# WiFiNode_Per_R00.net
KiCad netlist of a schematic drawn in Altium Designer
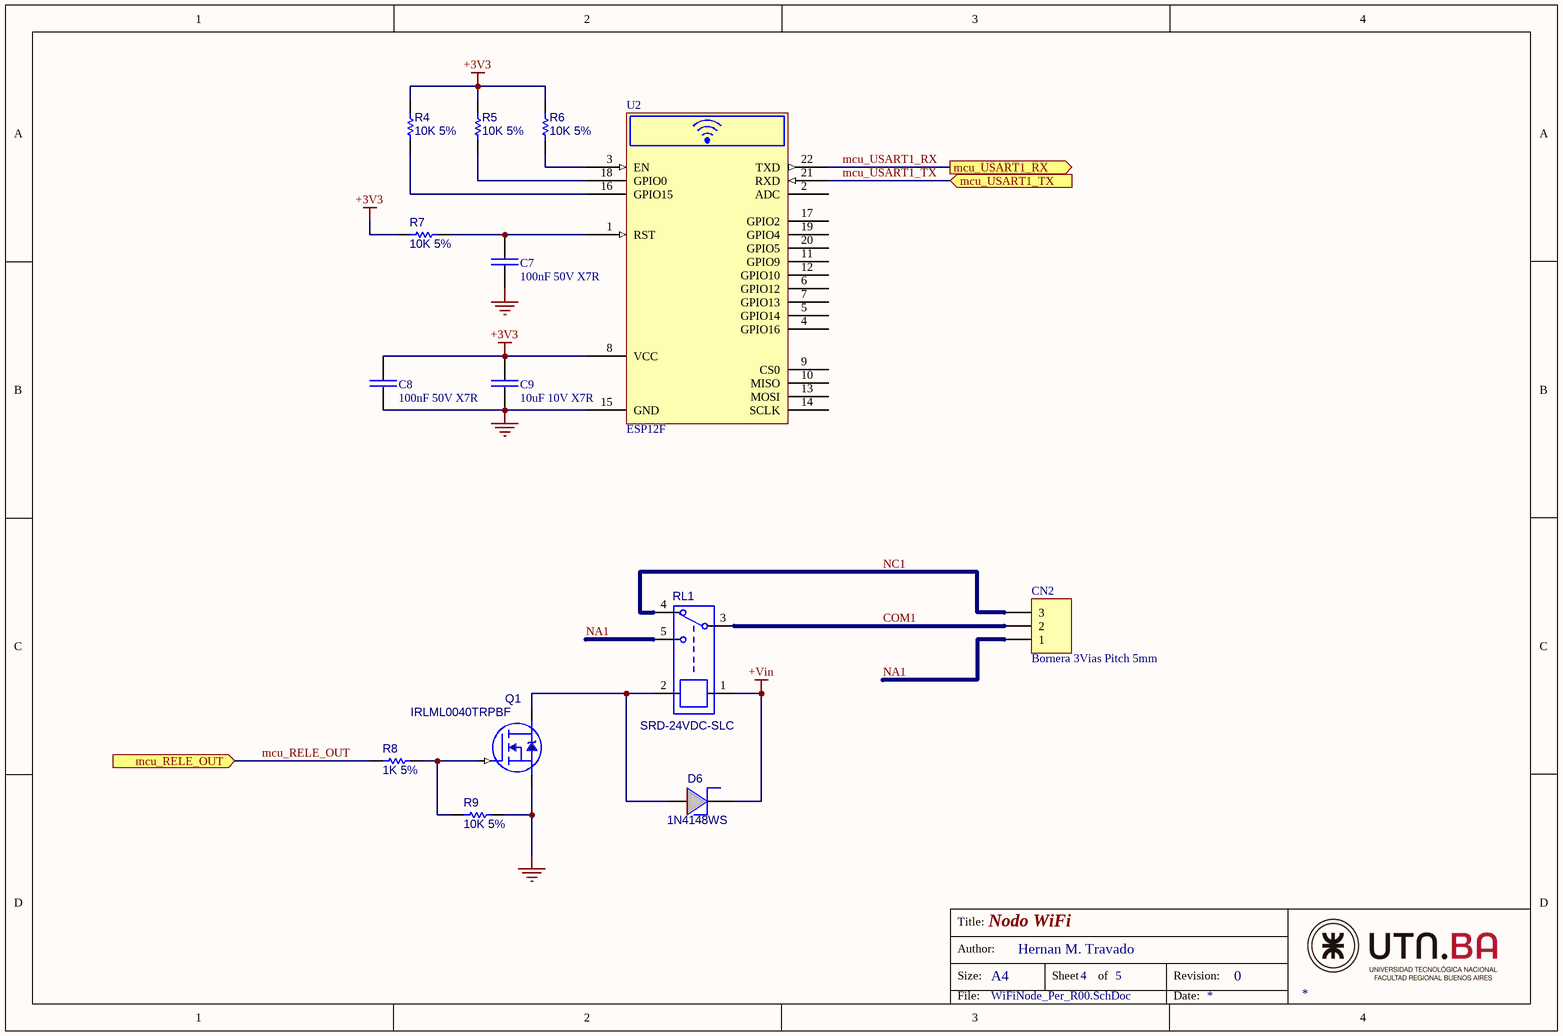
[diagram p0: WiFiNode_Per_R00.SchDoc]

(export (version "E")
  (design (tool "Eeschema 10.0.6"))
  (components
    (comp (ref "C7")
      (value "100nF 50V X7R")
      (footprint "C_0805")
      (description "Ceramic Capacitor")
      (libsource (lib "WiFiNode_R00") (part "Ceramic capacitor"))
    )
    (comp (ref "C8")
      (value "100nF 50V X7R")
      (footprint "C_0805")
      (description "Ceramic Capacitor")
      (libsource (lib "WiFiNode_R00") (part "Ceramic capacitor"))
    )
    (comp (ref "C9")
      (value "10uF 10V X7R")
      (footprint "C_0805")
      (description "Ceramic Capacitor")
      (libsource (lib "WiFiNode_R00") (part "Ceramic capacitor"))
    )
    (comp (ref "CN2")
      (value "Bornera 3Vias Pitch 5mm")
      (footprint "TerminalBlock_1x3_P5mm")
      (description "Connector Generic 3 Vias")
      (libsource (lib "WiFiNode_R00") (part "CONN_03P"))
    )
    (comp (ref "D6")
      (value "1N4148WS")
      (footprint "SOD_323")
      (description "Diode Shottky")
      (libsource (lib "WiFiNode_R00") (part "DIODO_SH"))
    )
    (comp (ref "Q1")
      (value "IRLML0040TRPBF")
      (footprint "SOT_23")
      (description "Mosfet N-Ch")
      (libsource (lib "WiFiNode_R00") (part "N_MOSFET_SOT23"))
    )
    (comp (ref "R4")
      (value "10K 5%")
      (footprint "R_0805")
      (description "Resistor")
      (libsource (lib "WiFiNode_R00") (part "Res1"))
    )
    (comp (ref "R5")
      (value "10K 5%")
      (footprint "R_0805")
      (description "Resistor")
      (libsource (lib "WiFiNode_R00") (part "Res1"))
    )
    (comp (ref "R6")
      (value "10K 5%")
      (footprint "R_0805")
      (description "Resistor")
      (libsource (lib "WiFiNode_R00") (part "Res1"))
    )
    (comp (ref "R7")
      (value "10K 5%")
      (footprint "R_0805")
      (description "Resistor")
      (libsource (lib "WiFiNode_R00") (part "Res1"))
    )
    (comp (ref "R8")
      (value "1K 5%")
      (footprint "R_0805")
      (description "Resistor")
      (libsource (lib "WiFiNode_R00") (part "Res1"))
    )
    (comp (ref "R9")
      (value "10K 5%")
      (footprint "R_0805")
      (description "Resistor")
      (libsource (lib "WiFiNode_R00") (part "Res1"))
    )
    (comp (ref "RL1")
      (value "SRD-24VDC-SLC")
      (footprint "943-1C")
      (description "Relay SPDT")
      (libsource (lib "WiFiNode_R00") (part "RELAY SPDT"))
    )
    (comp (ref "U2")
      (value "ESP12F")
      (footprint "ESP12F")
      (description "Wifi Module")
      (libsource (lib "WiFiNode_R00") (part "ESP12F Wifi Module"))
    )
  )
  (nets
    (net (code "1") (name "+3V3") (class "Default")
      (node (ref "C8") (pin "1") (pinfunction "1_1") (pintype "passive"))
      (node (ref "C9") (pin "1") (pinfunction "1_1") (pintype "passive"))
      (node (ref "R4") (pin "2") (pinfunction "2_2") (pintype "passive"))
      (node (ref "R5") (pin "2") (pinfunction "2_2") (pintype "passive"))
      (node (ref "R6") (pin "2") (pinfunction "2_2") (pintype "passive"))
      (node (ref "R7") (pin "2") (pinfunction "2_2") (pintype "passive"))
      (node (ref "U2") (pin "8") (pinfunction "VCC_8") (pintype "power_in"))
    )
    (net (code "2") (name "+Vin") (class "Default")
      (node (ref "D6") (pin "2") (pinfunction "K_2") (pintype "passive"))
      (node (ref "RL1") (pin "1") (pinfunction "1_1") (pintype "passive"))
    )
    (net (code "3") (name "/COM1") (class "Default")
      (node (ref "CN2") (pin "2") (pinfunction "2_2") (pintype "passive"))
      (node (ref "RL1") (pin "3") (pinfunction "3_3") (pintype "passive"))
    )
    (net (code "4") (name "/NA1") (class "Default")
      (node (ref "CN2") (pin "1") (pinfunction "1_1") (pintype "passive"))
      (node (ref "RL1") (pin "5") (pinfunction "5_5") (pintype "passive"))
    )
    (net (code "5") (name "/NC1") (class "Default")
      (node (ref "CN2") (pin "3") (pinfunction "3_3") (pintype "passive"))
      (node (ref "RL1") (pin "4") (pinfunction "4_4") (pintype "passive"))
    )
    (net (code "6") (name "/mcu_RELE_OUT") (class "Default")
      (node (ref "R8") (pin "2") (pinfunction "2_2") (pintype "passive"))
    )
    (net (code "7") (name "/mcu_USART1_RX") (class "Default")
      (node (ref "U2") (pin "22") (pinfunction "TXD_22") (pintype "output"))
    )
    (net (code "8") (name "/mcu_USART1_TX") (class "Default")
      (node (ref "U2") (pin "21") (pinfunction "RXD_21") (pintype "input"))
    )
    (net (code "9") (name "GND") (class "Default")
      (node (ref "C7") (pin "2") (pinfunction "2_2") (pintype "passive"))
      (node (ref "C8") (pin "2") (pinfunction "2_2") (pintype "passive"))
      (node (ref "C9") (pin "2") (pinfunction "2_2") (pintype "passive"))
      (node (ref "Q1") (pin "2") (pinfunction "SOURCE_2") (pintype "passive"))
      (node (ref "R9") (pin "1") (pinfunction "1_1") (pintype "passive"))
      (node (ref "U2") (pin "15") (pinfunction "GND_15") (pintype "power_in"))
    )
    (net (code "10") (name "Net-(D6-A)") (class "Default")
      (node (ref "D6") (pin "1") (pinfunction "A_1") (pintype "passive"))
      (node (ref "Q1") (pin "3") (pinfunction "DRAIN_3") (pintype "passive"))
      (node (ref "RL1") (pin "2") (pinfunction "2_2") (pintype "passive"))
    )
    (net (code "11") (name "Net-(Q1-GATE)") (class "Default")
      (node (ref "Q1") (pin "1") (pinfunction "GATE_1") (pintype "input"))
      (node (ref "R8") (pin "1") (pinfunction "1_1") (pintype "passive"))
      (node (ref "R9") (pin "2") (pinfunction "2_2") (pintype "passive"))
    )
    (net (code "12") (name "Net-(U2-EN)") (class "Default")
      (node (ref "R6") (pin "1") (pinfunction "1_1") (pintype "passive"))
      (node (ref "U2") (pin "3") (pinfunction "EN_3") (pintype "input"))
    )
    (net (code "13") (name "Net-(U2-GPIO0)") (class "Default")
      (node (ref "R5") (pin "1") (pinfunction "1_1") (pintype "passive"))
      (node (ref "U2") (pin "18") (pinfunction "GPIO0_18") (pintype "passive"))
    )
    (net (code "14") (name "Net-(U2-GPIO15)") (class "Default")
      (node (ref "R4") (pin "1") (pinfunction "1_1") (pintype "passive"))
      (node (ref "U2") (pin "16") (pinfunction "GPIO15_16") (pintype "passive"))
    )
    (net (code "15") (name "Net-(U2-RST)") (class "Default")
      (node (ref "C7") (pin "1") (pinfunction "1_1") (pintype "passive"))
      (node (ref "R7") (pin "1") (pinfunction "1_1") (pintype "passive"))
      (node (ref "U2") (pin "1") (pinfunction "RST_1") (pintype "input"))
    )
    (net (code "16") (name "unconnected-(U2-ADC-Pad2)") (class "Default")
      (node (ref "U2") (pin "2") (pinfunction "ADC_2") (pintype "passive"))
    )
    (net (code "17") (name "unconnected-(U2-CS0-Pad9)") (class "Default")
      (node (ref "U2") (pin "9") (pinfunction "CS0_9") (pintype "passive"))
    )
    (net (code "18") (name "unconnected-(U2-GPIO2-Pad17)") (class "Default")
      (node (ref "U2") (pin "17") (pinfunction "GPIO2_17") (pintype "passive"))
    )
    (net (code "19") (name "unconnected-(U2-GPIO4-Pad19)") (class "Default")
      (node (ref "U2") (pin "19") (pinfunction "GPIO4_19") (pintype "passive"))
    )
    (net (code "20") (name "unconnected-(U2-GPIO5-Pad20)") (class "Default")
      (node (ref "U2") (pin "20") (pinfunction "GPIO5_20") (pintype "passive"))
    )
    (net (code "21") (name "unconnected-(U2-GPIO9-Pad11)") (class "Default")
      (node (ref "U2") (pin "11") (pinfunction "GPIO9_11") (pintype "passive"))
    )
    (net (code "22") (name "unconnected-(U2-GPIO10-Pad12)") (class "Default")
      (node (ref "U2") (pin "12") (pinfunction "GPIO10_12") (pintype "passive"))
    )
    (net (code "23") (name "unconnected-(U2-GPIO12-Pad6)") (class "Default")
      (node (ref "U2") (pin "6") (pinfunction "GPIO12_6") (pintype "passive"))
    )
    (net (code "24") (name "unconnected-(U2-GPIO13-Pad7)") (class "Default")
      (node (ref "U2") (pin "7") (pinfunction "GPIO13_7") (pintype "passive"))
    )
    (net (code "25") (name "unconnected-(U2-GPIO14-Pad5)") (class "Default")
      (node (ref "U2") (pin "5") (pinfunction "GPIO14_5") (pintype "passive"))
    )
    (net (code "26") (name "unconnected-(U2-GPIO16-Pad4)") (class "Default")
      (node (ref "U2") (pin "4") (pinfunction "GPIO16_4") (pintype "passive"))
    )
    (net (code "27") (name "unconnected-(U2-MISO-Pad10)") (class "Default")
      (node (ref "U2") (pin "10") (pinfunction "MISO_10") (pintype "passive"))
    )
    (net (code "28") (name "unconnected-(U2-MOSI-Pad13)") (class "Default")
      (node (ref "U2") (pin "13") (pinfunction "MOSI_13") (pintype "passive"))
    )
    (net (code "29") (name "unconnected-(U2-SCLK-Pad14)") (class "Default")
      (node (ref "U2") (pin "14") (pinfunction "SCLK_14") (pintype "passive"))
    )
  )
)
